# SY_HR08_MCU_USB_V1_1.net
KiCad netlist of a schematic drawn in Altium Designer
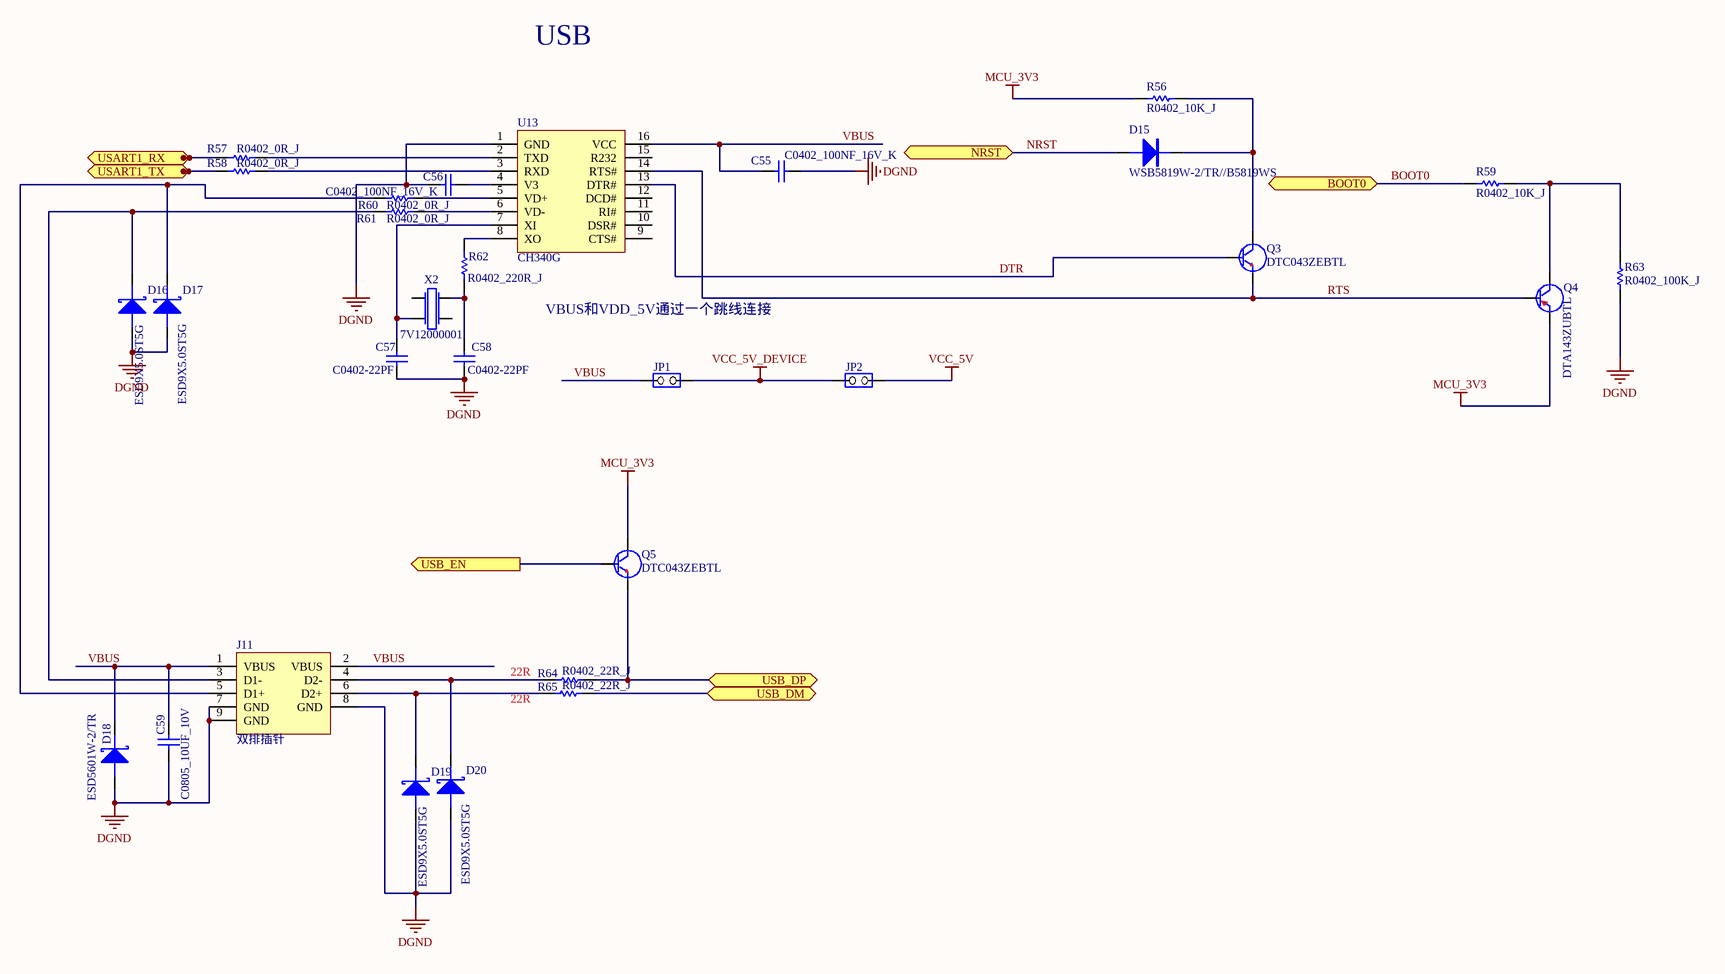
[diagram p0: SY_HR08_MCU_USB_V1.1.SchDoc]

(export (version "E")
  (design (tool "Eeschema 10.0.6"))
  (components
    (comp (ref "C55")
      (value "C0402_100NF_16V_K")
      (footprint "CAP0402_HQ")
      (description "电容_100nF_0402_X7R_16V_K")
      (libsource (lib "zhangky_sch") (part "C0402_100NF_16V_K"))
    )
    (comp (ref "C56")
      (value "C0402_100NF_16V_K")
      (footprint "CAP0402_HQ")
      (description "电容_100nF_0402_X7R_16V_K")
      (libsource (lib "zhangky_sch") (part "C0402_100NF_16V_K"))
    )
    (comp (ref "C57")
      (value "C0402-22PF")
      (footprint "CAP0402_HQ")
      (description "电容_22pF_0402_C0G_50V_J")
      (libsource (lib "zhangky_sch") (part "C0402-22PF"))
    )
    (comp (ref "C58")
      (value "C0402-22PF")
      (footprint "CAP0402_HQ")
      (description "电容_22pF_0402_C0G_50V_J")
      (libsource (lib "zhangky_sch") (part "C0402-22PF"))
    )
    (comp (ref "C59")
      (value "C0805_10UF_10V")
      (footprint "CAP0805-B")
      (description "电容_10uF_0805_X5R_10V_K")
      (libsource (lib "zhangky_sch") (part "C0805_10UF_10V"))
    )
    (comp (ref "D15")
      (value "WSB5819W-2/TR//B5819WS")
      (footprint "WSB5819W-2$2F$TR")
      (description "肖特基二极管_1A_SOD323")
      (fields
        (field (name "MANUFACTURER") "Will(韦尔)//ChangJiang Elec Tech(长电科技)")
        (field (name "PART NUMBER") "HQ11200391298")
      )
      (libsource (lib "zhangky_sch") (part "WSB5819W-2/TR//B5819WS"))
    )
    (comp (ref "D16")
      (value "ESD9X5.0ST5G")
      (footprint "ESD9X5.0ST5G")
      (description "TVS_单路_单向_5.0V_65pF")
      (fields (field (name "MANUFACTURER") "ONSEMI(安森美)") (field (name "PART NUMBER") "HQ11510010010"))
      (libsource (lib "zhangky_sch") (part "ESD9X5.0ST5G"))
    )
    (comp (ref "D17")
      (value "ESD9X5.0ST5G")
      (footprint "ESD9X5.0ST5G")
      (description "TVS_单路_单向_5.0V_65pF")
      (fields (field (name "MANUFACTURER") "ONSEMI(安森美)") (field (name "PART NUMBER") "HQ11510010010"))
      (libsource (lib "zhangky_sch") (part "ESD9X5.0ST5G"))
    )
    (comp (ref "D18")
      (value "ESD5601W-2/TR")
      (footprint "ESD5601W-2$2F$TR")
      (description "TVS_浪涌+静电二合一管_单向_7V_170pf")
      (fields (field (name "MANUFACTURER") "Will(韦尔)") (field (name "PART NUMBER") "HQ11510029000"))
      (libsource (lib "zhangky_sch") (part "ESD5601W-2/TR"))
    )
    (comp (ref "D19")
      (value "ESD9X5.0ST5G")
      (footprint "ESD9X5.0ST5G")
      (description "TVS_单路_单向_5.0V_65pF")
      (fields (field (name "MANUFACTURER") "ONSEMI(安森美)") (field (name "PART NUMBER") "HQ11510010010"))
      (libsource (lib "zhangky_sch") (part "ESD9X5.0ST5G"))
    )
    (comp (ref "D20")
      (value "ESD9X5.0ST5G")
      (footprint "ESD9X5.0ST5G")
      (description "TVS_单路_单向_5.0V_65pF")
      (fields (field (name "MANUFACTURER") "ONSEMI(安森美)") (field (name "PART NUMBER") "HQ11510010010"))
      (libsource (lib "zhangky_sch") (part "ESD9X5.0ST5G"))
    )
    (comp (ref "J11")
      (value "双排插针")
      (footprint "USB-9PIN")
      (description "主板9pin 双USB接口  2.54mm")
      (libsource (lib "zhangky_sch") (part "USB-9pin"))
    )
    (comp (ref "JP1")
      (value "单排插针")
      (footprint "CON1X2(2.54mm)")
      (libsource (lib "YS-F1Pro开发板主板") (part "JP2"))
    )
    (comp (ref "JP2")
      (value "单排插针")
      (footprint "CON1X2(2.54mm)")
      (libsource (lib "YS-F1Pro开发板主板") (part "JP2"))
    )
    (comp (ref "Q3")
      (value "DTC043ZEBTL")
      (footprint "DTC043ZEBTL$2F$$2F$DTC143ZE$2F$$2F$LDTC143ZET1G")
      (description "NPN三极管_100mA_EMT3F")
      (libsource (lib "zhangky_sch") (part "DTC043ZEBTL"))
    )
    (comp (ref "Q4")
      (value "DTA143ZUBTL")
      (footprint "UMT3F")
      (description "PNP三极管_100mA_UMT3F")
      (libsource (lib "zhangky_sch") (part "DTA143ZUBTL"))
    )
    (comp (ref "Q5")
      (value "DTC043ZEBTL")
      (footprint "DTC043ZEBTL$2F$$2F$DTC143ZE$2F$$2F$LDTC143ZET1G")
      (description "NPN三极管_100mA_EMT3F")
      (libsource (lib "zhangky_sch") (part "DTC043ZEBTL"))
    )
    (comp (ref "R56")
      (value "R0402_10K_J")
      (footprint "RES0402_HQ")
      (description "电阻10K(0402-0.0625W-J)")
      (libsource (lib "zhangky_sch") (part "R0402_10K_J"))
    )
    (comp (ref "R57")
      (value "R0402_0R_J")
      (footprint "RES0402_HQ")
      (description "电阻0R(0402-0.0625W-J)")
      (libsource (lib "zhangky_sch") (part "R0402_0R_J"))
    )
    (comp (ref "R58")
      (value "R0402_0R_J")
      (footprint "RES0402_HQ")
      (description "电阻0R(0402-0.0625W-J)")
      (libsource (lib "zhangky_sch") (part "R0402_0R_J"))
    )
    (comp (ref "R59")
      (value "R0402_10K_J")
      (footprint "RES0402_HQ")
      (description "电阻10K(0402-0.0625W-J)")
      (libsource (lib "zhangky_sch") (part "R0402_10K_J"))
    )
    (comp (ref "R60")
      (value "R0402_0R_J")
      (footprint "RES0402_HQ")
      (description "电阻0R(0402-0.0625W-J)")
      (libsource (lib "zhangky_sch") (part "R0402_0R_J"))
    )
    (comp (ref "R61")
      (value "R0402_0R_J")
      (footprint "RES0402_HQ")
      (description "电阻0R(0402-0.0625W-J)")
      (libsource (lib "zhangky_sch") (part "R0402_0R_J"))
    )
    (comp (ref "R62")
      (value "R0402_220R_J")
      (footprint "RES0402_HQ")
      (description "电阻220R(0402-0.0625W-J)")
      (libsource (lib "zhangky_sch") (part "R0402_220R_J"))
    )
    (comp (ref "R63")
      (value "R0402_100K_J")
      (footprint "RES0402_HQ")
      (description "电阻100K(0402-0.0625W-J)")
      (libsource (lib "zhangky_sch") (part "R0402_100K_J"))
    )
    (comp (ref "R64")
      (value "R0402_22R_J")
      (footprint "RES0402_HQ")
      (description "电阻0R(0402-0.0625W-J)")
      (libsource (lib "zhangky_sch") (part "R0402_0R_J"))
    )
    (comp (ref "R65")
      (value "R0402_22R_J")
      (footprint "RES0402_HQ")
      (description "电阻0R(0402-0.0625W-J)")
      (libsource (lib "zhangky_sch") (part "R0402_0R_J"))
    )
    (comp (ref "U13")
      (value "CH340G")
      (footprint "CH340G")
      (description "接口芯片_USB转UART")
      (libsource (lib "zhangky_sch") (part "CH340G"))
    )
    (comp (ref "X2")
      (value "7V12000001")
      (footprint "7V12000001")
      (description "TXC 3225 7V系列晶体")
      (fields (field (name "MANUFACTURER") "TXC"))
      (libsource (lib "zhangky_sch") (part "7V12000001"))
    )
  )
  (nets
    (net (code "1") (name "/BOOT0") (class "Default")
      (node (ref "R59") (pin "1") (pinfunction "1_1") (pintype "passive"))
    )
    (net (code "2") (name "/DTR") (class "Default")
      (node (ref "Q3") (pin "1") (pinfunction "B_1") (pintype "passive"))
      (node (ref "U13") (pin "13") (pinfunction "DTR#_13") (pintype "passive"))
    )
    (net (code "3") (name "/NRST") (class "Default")
      (node (ref "D15") (pin "2") (pinfunction "2_2") (pintype "passive"))
    )
    (net (code "4") (name "/RTS") (class "Default")
      (node (ref "Q3") (pin "2") (pinfunction "E_2") (pintype "passive"))
      (node (ref "Q4") (pin "1") (pinfunction "B_1") (pintype "passive"))
      (node (ref "U13") (pin "14") (pinfunction "RTS#_14") (pintype "passive"))
    )
    (net (code "5") (name "/USART1_RX") (class "Default")
      (node (ref "R57") (pin "1") (pinfunction "1_1") (pintype "passive"))
    )
    (net (code "6") (name "/USART1_TX") (class "Default")
      (node (ref "R58") (pin "1") (pinfunction "1_1") (pintype "passive"))
    )
    (net (code "7") (name "/USB_DM") (class "Default")
      (node (ref "R65") (pin "2") (pinfunction "2_2") (pintype "passive"))
    )
    (net (code "8") (name "/USB_DP") (class "Default")
      (node (ref "Q5") (pin "2") (pinfunction "E_2") (pintype "passive"))
      (node (ref "R64") (pin "2") (pinfunction "2_2") (pintype "passive"))
    )
    (net (code "9") (name "/USB_EN") (class "Default")
      (node (ref "Q5") (pin "1") (pinfunction "B_1") (pintype "passive"))
    )
    (net (code "10") (name "/VBUS") (class "Default")
      (node (ref "C55") (pin "1") (pinfunction "1_1") (pintype "passive"))
      (node (ref "C59") (pin "2") (pinfunction "2_2") (pintype "passive"))
      (node (ref "D18") (pin "1") (pinfunction "1_1") (pintype "passive"))
      (node (ref "J11") (pin "1") (pinfunction "VBUS_1") (pintype "passive"))
      (node (ref "J11") (pin "2") (pinfunction "VBUS_2") (pintype "passive"))
      (node (ref "JP1") (pin "1") (pinfunction "COMMON_1") (pintype "passive"))
      (node (ref "U13") (pin "16") (pinfunction "VCC_16") (pintype "passive"))
    )
    (net (code "11") (name "DGND") (class "Default")
      (node (ref "C55") (pin "2") (pinfunction "2_2") (pintype "passive"))
      (node (ref "C56") (pin "1") (pinfunction "1_1") (pintype "passive"))
      (node (ref "C57") (pin "1") (pinfunction "1_1") (pintype "passive"))
      (node (ref "C58") (pin "1") (pinfunction "1_1") (pintype "passive"))
      (node (ref "C59") (pin "1") (pinfunction "1_1") (pintype "passive"))
      (node (ref "D16") (pin "2") (pinfunction "2_2") (pintype "passive"))
      (node (ref "D17") (pin "2") (pinfunction "2_2") (pintype "passive"))
      (node (ref "D18") (pin "2") (pinfunction "2_2") (pintype "passive"))
      (node (ref "D19") (pin "2") (pinfunction "2_2") (pintype "passive"))
      (node (ref "D20") (pin "2") (pinfunction "2_2") (pintype "passive"))
      (node (ref "J11") (pin "7") (pinfunction "GND_7") (pintype "passive"))
      (node (ref "J11") (pin "8") (pinfunction "GND_8") (pintype "passive"))
      (node (ref "J11") (pin "9") (pinfunction "GND_9") (pintype "passive"))
      (node (ref "R63") (pin "1") (pinfunction "1_1") (pintype "passive"))
      (node (ref "U13") (pin "1") (pinfunction "GND_1") (pintype "passive"))
    )
    (net (code "12") (name "MCU_3V3") (class "Default")
      (node (ref "Q4") (pin "2") (pinfunction "E_2") (pintype "passive"))
      (node (ref "Q5") (pin "3") (pinfunction "C_3") (pintype "passive"))
      (node (ref "R56") (pin "1") (pinfunction "1_1") (pintype "passive"))
    )
    (net (code "13") (name "Net-(C58-Pad2)") (class "Default")
      (node (ref "C58") (pin "2") (pinfunction "2_2") (pintype "passive"))
      (node (ref "R62") (pin "1") (pinfunction "1_1") (pintype "passive"))
      (node (ref "X2") (pin "3") (pinfunction "3_3") (pintype "passive"))
    )
    (net (code "14") (name "Net-(J11-D1+)") (class "Default")
      (node (ref "D17") (pin "1") (pinfunction "1_1") (pintype "passive"))
      (node (ref "J11") (pin "5") (pinfunction "D1+_5") (pintype "passive"))
      (node (ref "R60") (pin "1") (pinfunction "1_1") (pintype "passive"))
    )
    (net (code "15") (name "Net-(J11-D1-)") (class "Default")
      (node (ref "D16") (pin "1") (pinfunction "1_1") (pintype "passive"))
      (node (ref "J11") (pin "3") (pinfunction "D1-_3") (pintype "passive"))
      (node (ref "R61") (pin "1") (pinfunction "1_1") (pintype "passive"))
    )
    (net (code "16") (name "Net-(J11-D2+)") (class "Default")
      (node (ref "D19") (pin "1") (pinfunction "1_1") (pintype "passive"))
      (node (ref "J11") (pin "6") (pinfunction "D2+_6") (pintype "passive"))
      (node (ref "R65") (pin "1") (pinfunction "1_1") (pintype "passive"))
    )
    (net (code "17") (name "Net-(J11-D2-)") (class "Default")
      (node (ref "D20") (pin "1") (pinfunction "1_1") (pintype "passive"))
      (node (ref "J11") (pin "4") (pinfunction "D2-_4") (pintype "passive"))
      (node (ref "R64") (pin "1") (pinfunction "1_1") (pintype "passive"))
    )
    (net (code "18") (name "Net-(Q3-C)") (class "Default")
      (node (ref "D15") (pin "1") (pinfunction "1_1") (pintype "passive"))
      (node (ref "Q3") (pin "3") (pinfunction "C_3") (pintype "passive"))
      (node (ref "R56") (pin "2") (pinfunction "2_2") (pintype "passive"))
    )
    (net (code "19") (name "Net-(Q4-C)") (class "Default")
      (node (ref "Q4") (pin "3") (pinfunction "C_3") (pintype "passive"))
      (node (ref "R59") (pin "2") (pinfunction "2_2") (pintype "passive"))
      (node (ref "R63") (pin "2") (pinfunction "2_2") (pintype "passive"))
    )
    (net (code "20") (name "Net-(U13-RXD)") (class "Default")
      (node (ref "R58") (pin "2") (pinfunction "2_2") (pintype "passive"))
      (node (ref "U13") (pin "3") (pinfunction "RXD_3") (pintype "passive"))
    )
    (net (code "21") (name "Net-(U13-TXD)") (class "Default")
      (node (ref "R57") (pin "2") (pinfunction "2_2") (pintype "passive"))
      (node (ref "U13") (pin "2") (pinfunction "TXD_2") (pintype "passive"))
    )
    (net (code "22") (name "Net-(U13-V3)") (class "Default")
      (node (ref "C56") (pin "2") (pinfunction "2_2") (pintype "passive"))
      (node (ref "U13") (pin "4") (pinfunction "V3_4") (pintype "passive"))
    )
    (net (code "23") (name "Net-(U13-VD+)") (class "Default")
      (node (ref "R60") (pin "2") (pinfunction "2_2") (pintype "passive"))
      (node (ref "U13") (pin "5") (pinfunction "VD+_5") (pintype "passive"))
    )
    (net (code "24") (name "Net-(U13-VD-)") (class "Default")
      (node (ref "R61") (pin "2") (pinfunction "2_2") (pintype "passive"))
      (node (ref "U13") (pin "6") (pinfunction "VD-_6") (pintype "passive"))
    )
    (net (code "25") (name "Net-(U13-XI)") (class "Default")
      (node (ref "C57") (pin "2") (pinfunction "2_2") (pintype "passive"))
      (node (ref "U13") (pin "7") (pinfunction "XI_7") (pintype "passive"))
      (node (ref "X2") (pin "1") (pinfunction "1_1") (pintype "passive"))
    )
    (net (code "26") (name "Net-(U13-XO)") (class "Default")
      (node (ref "R62") (pin "2") (pinfunction "2_2") (pintype "passive"))
      (node (ref "U13") (pin "8") (pinfunction "XO_8") (pintype "passive"))
    )
    (net (code "27") (name "VCC_5V") (class "Default")
      (node (ref "JP2") (pin "2") (pinfunction "NO_2") (pintype "passive"))
    )
    (net (code "28") (name "VCC_5V_DEVICE") (class "Default")
      (node (ref "JP1") (pin "2") (pinfunction "NO_2") (pintype "passive"))
      (node (ref "JP2") (pin "1") (pinfunction "COMMON_1") (pintype "passive"))
    )
    (net (code "29") (name "unconnected-(U13-CTS#-Pad9)") (class "Default")
      (node (ref "U13") (pin "9") (pinfunction "CTS#_9") (pintype "passive"))
    )
    (net (code "30") (name "unconnected-(U13-DCD#-Pad12)") (class "Default")
      (node (ref "U13") (pin "12") (pinfunction "DCD#_12") (pintype "passive"))
    )
    (net (code "31") (name "unconnected-(U13-DSR#-Pad10)") (class "Default")
      (node (ref "U13") (pin "10") (pinfunction "DSR#_10") (pintype "passive"))
    )
    (net (code "32") (name "unconnected-(U13-R232-Pad15)") (class "Default")
      (node (ref "U13") (pin "15") (pinfunction "R232_15") (pintype "passive"))
    )
    (net (code "33") (name "unconnected-(U13-RI#-Pad11)") (class "Default")
      (node (ref "U13") (pin "11") (pinfunction "RI#_11") (pintype "passive"))
    )
    (net (code "34") (name "unconnected-(X2-Pad2)") (class "Default")
      (node (ref "X2") (pin "2") (pinfunction "2_2") (pintype "passive"))
    )
    (net (code "35") (name "unconnected-(X2-Pad4)") (class "Default")
      (node (ref "X2") (pin "4") (pinfunction "4_4") (pintype "passive"))
    )
  )
)
